# pcm2707_test_v0001.net
KiCad netlist of a schematic drawn in EAGLE
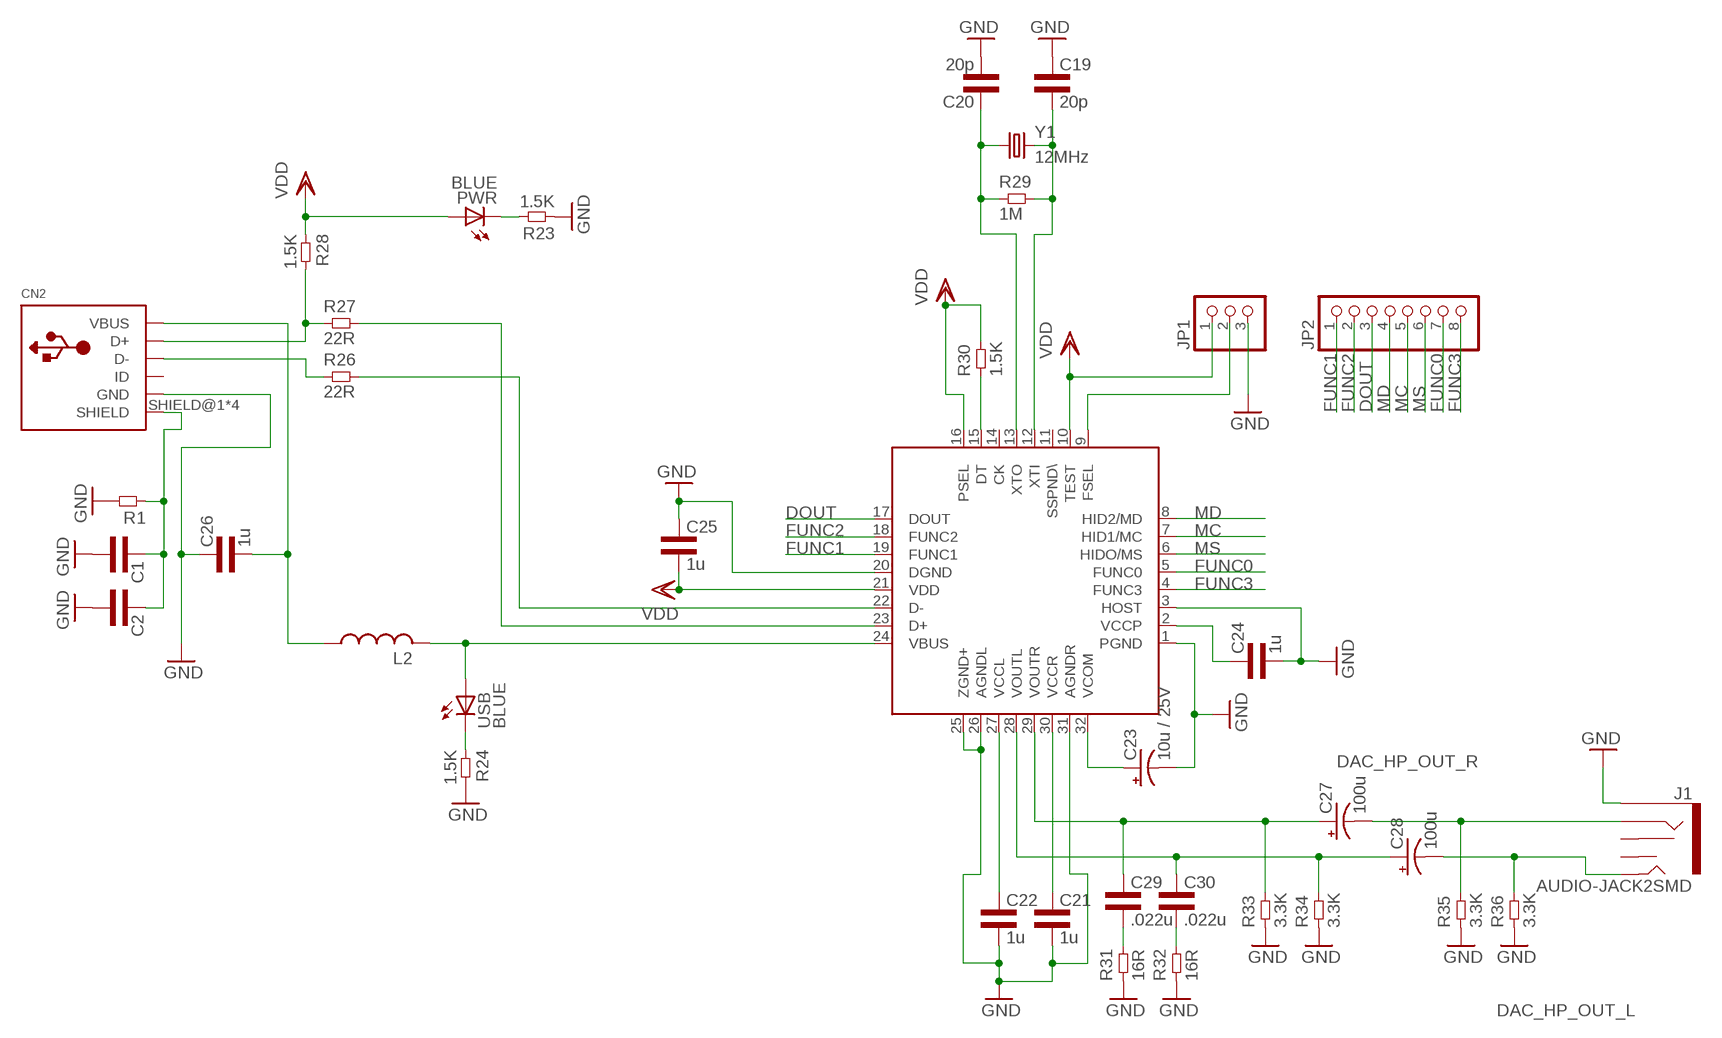
[diagram p0: schematic, sheet 1]

(export (version "E")
  (design (tool "Eeschema 10.0.6"))
  (components
    (comp (ref "C1")
      (value "CAP0603L3")
      (footprint "eagle-import:0603L3")
      (libsource (lib "eagle-import") (part "CAP0603L3"))
    )
    (comp (ref "C2")
      (value "CAP0603L3")
      (footprint "eagle-import:0603L3")
      (libsource (lib "eagle-import") (part "CAP0603L3"))
    )
    (comp (ref "C19")
      (value "20p")
      (footprint "eagle-import:0603L3")
      (libsource (lib "eagle-import") (part "CAP0603L3"))
    )
    (comp (ref "C20")
      (value "20p")
      (footprint "eagle-import:0603L3")
      (libsource (lib "eagle-import") (part "CAP0603L3"))
    )
    (comp (ref "C21")
      (value "1u")
      (footprint "eagle-import:0603L3")
      (libsource (lib "eagle-import") (part "CAP0603L3"))
    )
    (comp (ref "C22")
      (value "1u")
      (footprint "eagle-import:0603L3")
      (libsource (lib "eagle-import") (part "CAP0603L3"))
    )
    (comp (ref "C23")
      (value "10u / 25V")
      (footprint "eagle-import:E1,8-4")
      (libsource (lib "eagle-import") (part "CPOL-USE1.8-4"))
    )
    (comp (ref "C24")
      (value "1u")
      (footprint "eagle-import:0603L3")
      (libsource (lib "eagle-import") (part "CAP0603L3"))
    )
    (comp (ref "C25")
      (value "1u")
      (footprint "eagle-import:0603L3")
      (libsource (lib "eagle-import") (part "CAP0603L3"))
    )
    (comp (ref "C26")
      (value "1u")
      (footprint "eagle-import:0603L3")
      (libsource (lib "eagle-import") (part "CAP0603L3"))
    )
    (comp (ref "C27")
      (value "100u")
      (footprint "eagle-import:E2-5")
      (libsource (lib "eagle-import") (part "CPOL-USE2-5"))
    )
    (comp (ref "C28")
      (value "100u")
      (footprint "eagle-import:E2-5")
      (libsource (lib "eagle-import") (part "CPOL-USE2-5"))
    )
    (comp (ref "C29")
      (value ".022u")
      (footprint "eagle-import:0603L3")
      (libsource (lib "eagle-import") (part "CAP0603L3"))
    )
    (comp (ref "C30")
      (value ".022u")
      (footprint "eagle-import:0603L3")
      (libsource (lib "eagle-import") (part "CAP0603L3"))
    )
    (comp (ref "CN2")
      (value "USBMINIB")
      (footprint "eagle-import:USB-MINIB")
      (libsource (lib "eagle-import") (part "USBMINIB"))
    )
    (comp (ref "J1")
      (value "AUDIO-JACK2SMD")
      (footprint "eagle-import:AUDIO-JACK-3.5MM-SMD")
      (libsource (lib "eagle-import") (part "AUDIO-JACK2SMD"))
    )
    (comp (ref "JP1")
      (value "PINHD-1X3")
      (footprint "eagle-import:1X03")
      (libsource (lib "eagle-import") (part "PINHD-1X3"))
    )
    (comp (ref "JP2")
      (value "PINHD-1X8")
      (footprint "eagle-import:1X08")
      (libsource (lib "eagle-import") (part "PINHD-1X8"))
    )
    (comp (ref "L2")
      (value "RCL_L-USL3225M")
      (footprint "eagle-import:RCL_L3225M")
      (libsource (lib "eagle-import") (part "RCL_L-USL3225M"))
    )
    (comp (ref "PWR")
      (value "BLUE")
      (footprint "eagle-import:LED-0603")
      (libsource (lib "eagle-import") (part "LED-BLUE0603"))
    )
    (comp (ref "R1")
      (value "RES0603L3")
      (footprint "eagle-import:0603L3")
      (libsource (lib "eagle-import") (part "RES0603L3"))
    )
    (comp (ref "R23")
      (value "1.5K")
      (footprint "eagle-import:0603L3")
      (libsource (lib "eagle-import") (part "RES0603L3"))
    )
    (comp (ref "R24")
      (value "1.5K")
      (footprint "eagle-import:0603L3")
      (libsource (lib "eagle-import") (part "RES0603L3"))
    )
    (comp (ref "R26")
      (value "22R")
      (footprint "eagle-import:0603L3")
      (libsource (lib "eagle-import") (part "RES0603L3"))
    )
    (comp (ref "R27")
      (value "22R")
      (footprint "eagle-import:0603L3")
      (libsource (lib "eagle-import") (part "RES0603L3"))
    )
    (comp (ref "R28")
      (value "1.5K")
      (footprint "eagle-import:0603L3")
      (libsource (lib "eagle-import") (part "RES0603L3"))
    )
    (comp (ref "R29")
      (value "1M")
      (footprint "eagle-import:0603L3")
      (libsource (lib "eagle-import") (part "RES0603L3"))
    )
    (comp (ref "R30")
      (value "1.5K")
      (footprint "eagle-import:0603L3")
      (libsource (lib "eagle-import") (part "RES0603L3"))
    )
    (comp (ref "R31")
      (value "16R")
      (footprint "eagle-import:0603L3")
      (libsource (lib "eagle-import") (part "RES0603L3"))
    )
    (comp (ref "R32")
      (value "16R")
      (footprint "eagle-import:0603L3")
      (libsource (lib "eagle-import") (part "RES0603L3"))
    )
    (comp (ref "R33")
      (value "3.3K")
      (footprint "eagle-import:0603L3")
      (libsource (lib "eagle-import") (part "RES0603L3"))
    )
    (comp (ref "R34")
      (value "3.3K")
      (footprint "eagle-import:0603L3")
      (libsource (lib "eagle-import") (part "RES0603L3"))
    )
    (comp (ref "R35")
      (value "3.3K")
      (footprint "eagle-import:0603L3")
      (libsource (lib "eagle-import") (part "RES0603L3"))
    )
    (comp (ref "R36")
      (value "3.3K")
      (footprint "eagle-import:0603L3")
      (libsource (lib "eagle-import") (part "RES0603L3"))
    )
    (comp (ref "U$1")
      (value "PCM2707_V1_PCM2704C_PCM2707")
      (footprint "eagle-import:PCM2707_V1_PCM2704C_PCM2707")
      (libsource (lib "eagle-import") (part "PCM2707_V1_PCM2704C_PCM2707"))
    )
    (comp (ref "USB")
      (value "BLUE")
      (footprint "eagle-import:LED-0603")
      (libsource (lib "eagle-import") (part "LED-BLUE0603"))
    )
    (comp (ref "Y1")
      (value "12MHz")
      (footprint "eagle-import:HC49US")
      (libsource (lib "eagle-import") (part "CRYSTALHC49US"))
    )
  )
  (nets
    (net (code "1") (name "/DAC_HP_OUT_L") (class "Default")
      (node (ref "C28") (pin "-") (pinfunction "-_-") (pintype "passive"))
      (node (ref "J1") (pin "TIP") (pinfunction "TIP_TIP") (pintype "bidirectional"))
      (node (ref "R36") (pin "P$2") (pinfunction "2_P$2") (pintype "bidirectional"))
    )
    (net (code "2") (name "/DAC_HP_OUT_R") (class "Default")
      (node (ref "C27") (pin "-") (pinfunction "-_-") (pintype "passive"))
      (node (ref "J1") (pin "RING") (pinfunction "RING_RING") (pintype "bidirectional"))
      (node (ref "R35") (pin "P$2") (pinfunction "2_P$2") (pintype "bidirectional"))
    )
    (net (code "3") (name "/DOUT") (class "Default")
      (node (ref "JP2") (pin "3") (pinfunction "3_3") (pintype "passive"))
      (node (ref "U$1") (pin "17") (pinfunction "DOUT_17") (pintype "bidirectional"))
    )
    (net (code "4") (name "/FUNC0") (class "Default")
      (node (ref "JP2") (pin "7") (pinfunction "7_7") (pintype "passive"))
      (node (ref "U$1") (pin "5") (pinfunction "FUNC0_5") (pintype "bidirectional"))
    )
    (net (code "5") (name "/FUNC1") (class "Default")
      (node (ref "JP2") (pin "1") (pinfunction "1_1") (pintype "passive"))
      (node (ref "U$1") (pin "19") (pinfunction "FUNC1_19") (pintype "bidirectional"))
    )
    (net (code "6") (name "/FUNC2") (class "Default")
      (node (ref "JP2") (pin "2") (pinfunction "2_2") (pintype "passive"))
      (node (ref "U$1") (pin "18") (pinfunction "FUNC2_18") (pintype "bidirectional"))
    )
    (net (code "7") (name "/FUNC3") (class "Default")
      (node (ref "JP2") (pin "8") (pinfunction "8_8") (pintype "passive"))
      (node (ref "U$1") (pin "4") (pinfunction "FUNC3_4") (pintype "bidirectional"))
    )
    (net (code "8") (name "/MC") (class "Default")
      (node (ref "JP2") (pin "5") (pinfunction "5_5") (pintype "passive"))
      (node (ref "U$1") (pin "7") (pinfunction "HID1/MC_7") (pintype "bidirectional"))
    )
    (net (code "9") (name "/MD") (class "Default")
      (node (ref "JP2") (pin "4") (pinfunction "4_4") (pintype "passive"))
      (node (ref "U$1") (pin "8") (pinfunction "HID2/MD_8") (pintype "bidirectional"))
    )
    (net (code "10") (name "/MS") (class "Default")
      (node (ref "JP2") (pin "6") (pinfunction "6_6") (pintype "passive"))
      (node (ref "U$1") (pin "6") (pinfunction "HIDO/MS_6") (pintype "bidirectional"))
    )
    (net (code "11") (name "GND") (class "Default")
      (node (ref "C1") (pin "P$2") (pinfunction "2_P$2") (pintype "bidirectional"))
      (node (ref "C19") (pin "P$1") (pinfunction "1_P$1") (pintype "bidirectional"))
      (node (ref "C2") (pin "P$2") (pinfunction "2_P$2") (pintype "bidirectional"))
      (node (ref "C20") (pin "P$2") (pinfunction "2_P$2") (pintype "bidirectional"))
      (node (ref "C21") (pin "P$2") (pinfunction "2_P$2") (pintype "bidirectional"))
      (node (ref "C22") (pin "P$2") (pinfunction "2_P$2") (pintype "bidirectional"))
      (node (ref "C23") (pin "-") (pinfunction "-_-") (pintype "passive"))
      (node (ref "C24") (pin "P$2") (pinfunction "2_P$2") (pintype "bidirectional"))
      (node (ref "C25") (pin "P$1") (pinfunction "1_P$1") (pintype "bidirectional"))
      (node (ref "C26") (pin "P$1") (pinfunction "1_P$1") (pintype "bidirectional"))
      (node (ref "CN2") (pin "GND") (pinfunction "GND_GND") (pintype "power_in"))
      (node (ref "J1") (pin "SLEEVE") (pinfunction "SLEEVE_SLEEVE") (pintype "bidirectional"))
      (node (ref "JP1") (pin "3") (pinfunction "3_3") (pintype "passive"))
      (node (ref "R1") (pin "P$2") (pinfunction "2_P$2") (pintype "bidirectional"))
      (node (ref "R23") (pin "P$1") (pinfunction "1_P$1") (pintype "bidirectional"))
      (node (ref "R24") (pin "P$2") (pinfunction "2_P$2") (pintype "bidirectional"))
      (node (ref "R31") (pin "P$1") (pinfunction "1_P$1") (pintype "bidirectional"))
      (node (ref "R32") (pin "P$1") (pinfunction "1_P$1") (pintype "bidirectional"))
      (node (ref "R33") (pin "P$1") (pinfunction "1_P$1") (pintype "bidirectional"))
      (node (ref "R34") (pin "P$1") (pinfunction "1_P$1") (pintype "bidirectional"))
      (node (ref "R35") (pin "P$1") (pinfunction "1_P$1") (pintype "bidirectional"))
      (node (ref "R36") (pin "P$1") (pinfunction "1_P$1") (pintype "bidirectional"))
      (node (ref "U$1") (pin "1") (pinfunction "PGND_1") (pintype "bidirectional"))
      (node (ref "U$1") (pin "20") (pinfunction "DGND_20") (pintype "bidirectional"))
      (node (ref "U$1") (pin "25") (pinfunction "ZGND+_25") (pintype "bidirectional"))
      (node (ref "U$1") (pin "26") (pinfunction "AGNDL_26") (pintype "bidirectional"))
      (node (ref "U$1") (pin "3") (pinfunction "HOST_3") (pintype "bidirectional"))
      (node (ref "U$1") (pin "31") (pinfunction "AGNDR_31") (pintype "bidirectional"))
    )
    (net (code "12") (name "Net-(C1-1)") (class "Default")
      (node (ref "C1") (pin "P$1") (pinfunction "1_P$1") (pintype "bidirectional"))
      (node (ref "C2") (pin "P$1") (pinfunction "1_P$1") (pintype "bidirectional"))
      (node (ref "CN2") (pin "SHIELD@1") (pinfunction "SHIELD_SHIELD@1") (pintype "bidirectional"))
      (node (ref "CN2") (pin "SHIELD@2") (pinfunction "SHIELD_SHIELD@2") (pintype "bidirectional"))
      (node (ref "CN2") (pin "SHIELD@3") (pinfunction "SHIELD_SHIELD@3") (pintype "bidirectional"))
      (node (ref "CN2") (pin "SHIELD@4") (pinfunction "SHIELD_SHIELD@4") (pintype "bidirectional"))
      (node (ref "R1") (pin "P$1") (pinfunction "1_P$1") (pintype "bidirectional"))
    )
    (net (code "13") (name "Net-(C19-2)") (class "Default")
      (node (ref "C19") (pin "P$2") (pinfunction "2_P$2") (pintype "bidirectional"))
      (node (ref "R29") (pin "P$2") (pinfunction "2_P$2") (pintype "bidirectional"))
      (node (ref "U$1") (pin "12") (pinfunction "XTI_12") (pintype "bidirectional"))
      (node (ref "Y1") (pin "2") (pinfunction "2_2") (pintype "passive"))
    )
    (net (code "14") (name "Net-(C20-1)") (class "Default")
      (node (ref "C20") (pin "P$1") (pinfunction "1_P$1") (pintype "bidirectional"))
      (node (ref "R29") (pin "P$1") (pinfunction "1_P$1") (pintype "bidirectional"))
      (node (ref "U$1") (pin "13") (pinfunction "XTO_13") (pintype "bidirectional"))
      (node (ref "Y1") (pin "1") (pinfunction "1_1") (pintype "passive"))
    )
    (net (code "15") (name "Net-(C21-1)") (class "Default")
      (node (ref "C21") (pin "P$1") (pinfunction "1_P$1") (pintype "bidirectional"))
      (node (ref "U$1") (pin "30") (pinfunction "VCCR_30") (pintype "bidirectional"))
    )
    (net (code "16") (name "Net-(C22-1)") (class "Default")
      (node (ref "C22") (pin "P$1") (pinfunction "1_P$1") (pintype "bidirectional"))
      (node (ref "U$1") (pin "27") (pinfunction "VCCL_27") (pintype "bidirectional"))
    )
    (net (code "17") (name "Net-(C24-1)") (class "Default")
      (node (ref "C24") (pin "P$1") (pinfunction "1_P$1") (pintype "bidirectional"))
      (node (ref "U$1") (pin "2") (pinfunction "VCCP_2") (pintype "bidirectional"))
    )
    (net (code "18") (name "Net-(C26-2)") (class "Default")
      (node (ref "C26") (pin "P$2") (pinfunction "2_P$2") (pintype "bidirectional"))
      (node (ref "CN2") (pin "VBUS") (pinfunction "VBUS_VBUS") (pintype "power_in"))
      (node (ref "L2") (pin "1") (pinfunction "1_1") (pintype "passive"))
    )
    (net (code "19") (name "Net-(C29-1)") (class "Default")
      (node (ref "C27") (pin "+") (pinfunction "+_+") (pintype "passive"))
      (node (ref "C29") (pin "P$1") (pinfunction "1_P$1") (pintype "bidirectional"))
      (node (ref "R33") (pin "P$2") (pinfunction "2_P$2") (pintype "bidirectional"))
      (node (ref "U$1") (pin "29") (pinfunction "VOUTR_29") (pintype "bidirectional"))
    )
    (net (code "20") (name "Net-(C29-2)") (class "Default")
      (node (ref "C29") (pin "P$2") (pinfunction "2_P$2") (pintype "bidirectional"))
      (node (ref "R31") (pin "P$2") (pinfunction "2_P$2") (pintype "bidirectional"))
    )
    (net (code "21") (name "Net-(C30-1)") (class "Default")
      (node (ref "C28") (pin "+") (pinfunction "+_+") (pintype "passive"))
      (node (ref "C30") (pin "P$1") (pinfunction "1_P$1") (pintype "bidirectional"))
      (node (ref "R34") (pin "P$2") (pinfunction "2_P$2") (pintype "bidirectional"))
      (node (ref "U$1") (pin "28") (pinfunction "VOUTL_28") (pintype "bidirectional"))
    )
    (net (code "22") (name "Net-(C30-2)") (class "Default")
      (node (ref "C30") (pin "P$2") (pinfunction "2_P$2") (pintype "bidirectional"))
      (node (ref "R32") (pin "P$2") (pinfunction "2_P$2") (pintype "bidirectional"))
    )
    (net (code "23") (name "Net-(R23-2)") (class "Default")
      (node (ref "PWR") (pin "C") (pinfunction "C_C") (pintype "passive"))
      (node (ref "R23") (pin "P$2") (pinfunction "2_P$2") (pintype "bidirectional"))
    )
    (net (code "24") (name "Net-(R24-1)") (class "Default")
      (node (ref "R24") (pin "P$1") (pinfunction "1_P$1") (pintype "bidirectional"))
      (node (ref "USB") (pin "C") (pinfunction "C_C") (pintype "passive"))
    )
    (net (code "25") (name "Net-(R26-1)") (class "Default")
      (node (ref "CN2") (pin "D-") (pinfunction "D-_D-") (pintype "bidirectional"))
      (node (ref "R26") (pin "P$1") (pinfunction "1_P$1") (pintype "bidirectional"))
    )
    (net (code "26") (name "Net-(R26-2)") (class "Default")
      (node (ref "R26") (pin "P$2") (pinfunction "2_P$2") (pintype "bidirectional"))
      (node (ref "U$1") (pin "22") (pinfunction "D-_22") (pintype "bidirectional"))
    )
    (net (code "27") (name "Net-(R27-1)") (class "Default")
      (node (ref "CN2") (pin "D+") (pinfunction "D+_D+") (pintype "bidirectional"))
      (node (ref "R27") (pin "P$1") (pinfunction "1_P$1") (pintype "bidirectional"))
      (node (ref "R28") (pin "P$2") (pinfunction "2_P$2") (pintype "bidirectional"))
    )
    (net (code "28") (name "Net-(R27-2)") (class "Default")
      (node (ref "R27") (pin "P$2") (pinfunction "2_P$2") (pintype "bidirectional"))
      (node (ref "U$1") (pin "23") (pinfunction "D+_23") (pintype "bidirectional"))
    )
    (net (code "29") (name "Net-(R30-1)") (class "Default")
      (node (ref "R30") (pin "P$1") (pinfunction "1_P$1") (pintype "bidirectional"))
      (node (ref "U$1") (pin "15") (pinfunction "DT_15") (pintype "bidirectional"))
    )
    (net (code "30") (name "Net-(U$1-FSEL)") (class "Default")
      (node (ref "JP1") (pin "2") (pinfunction "2_2") (pintype "passive"))
      (node (ref "U$1") (pin "9") (pinfunction "FSEL_9") (pintype "bidirectional"))
    )
    (net (code "31") (name "Net-(U$1-VBUS)") (class "Default")
      (node (ref "L2") (pin "2") (pinfunction "2_2") (pintype "passive"))
      (node (ref "U$1") (pin "24") (pinfunction "VBUS_24") (pintype "bidirectional"))
      (node (ref "USB") (pin "A") (pinfunction "A_A") (pintype "passive"))
    )
    (net (code "32") (name "Net-(U$1-VCOM)") (class "Default")
      (node (ref "C23") (pin "+") (pinfunction "+_+") (pintype "passive"))
      (node (ref "U$1") (pin "32") (pinfunction "VCOM_32") (pintype "bidirectional"))
    )
    (net (code "33") (name "VDD") (class "Default")
      (node (ref "C25") (pin "P$2") (pinfunction "2_P$2") (pintype "bidirectional"))
      (node (ref "JP1") (pin "1") (pinfunction "1_1") (pintype "passive"))
      (node (ref "PWR") (pin "A") (pinfunction "A_A") (pintype "passive"))
      (node (ref "R28") (pin "P$1") (pinfunction "1_P$1") (pintype "bidirectional"))
      (node (ref "R30") (pin "P$2") (pinfunction "2_P$2") (pintype "bidirectional"))
      (node (ref "U$1") (pin "10") (pinfunction "TEST_10") (pintype "bidirectional"))
      (node (ref "U$1") (pin "16") (pinfunction "PSEL_16") (pintype "bidirectional"))
      (node (ref "U$1") (pin "21") (pinfunction "VDD_21") (pintype "bidirectional"))
    )
    (net (code "34") (name "unconnected-(CN2-PadID)") (class "Default")
      (node (ref "CN2") (pin "ID") (pinfunction "ID_ID") (pintype "bidirectional"))
    )
    (net (code "35") (name "unconnected-(J1-PadRSH)") (class "Default")
      (node (ref "J1") (pin "RSH") (pinfunction "RSH_RSH") (pintype "bidirectional"))
    )
    (net (code "36") (name "unconnected-(J1-PadTSH)") (class "Default")
      (node (ref "J1") (pin "TSH") (pinfunction "TSH_TSH") (pintype "bidirectional"))
    )
    (net (code "37") (name "unconnected-(U$1-CK-Pad14)") (class "Default")
      (node (ref "U$1") (pin "14") (pinfunction "CK_14") (pintype "bidirectional"))
    )
    (net (code "38") (name "unconnected-(U$1-SSPND\\-Pad11)") (class "Default")
      (node (ref "U$1") (pin "11") (pinfunction "SSPND\\_11") (pintype "bidirectional"))
    )
  )
)
